# Linear_Regulator_LT3042.net
KiCad netlist of a schematic drawn in EAGLE
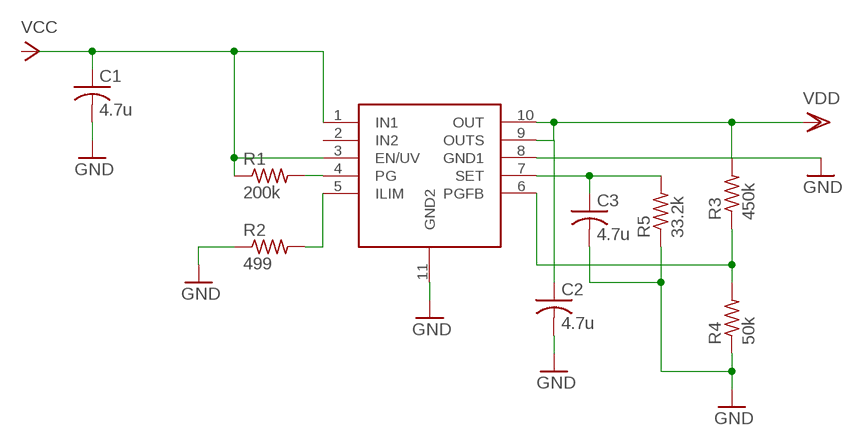
[diagram p0: schematic, sheet 1]

(export (version "E")
  (design (tool "Eeschema 10.0.6"))
  (components
    (comp (ref "C1")
      (value "4.7u")
      (footprint "eagle-import:C0603")
      (libsource (lib "eagle-import") (part "C-USC0603"))
    )
    (comp (ref "C2")
      (value "4.7u")
      (footprint "eagle-import:C0603")
      (libsource (lib "eagle-import") (part "C-USC0603"))
    )
    (comp (ref "C3")
      (value "4.7u")
      (footprint "eagle-import:C0603")
      (libsource (lib "eagle-import") (part "C-USC0603"))
    )
    (comp (ref "R1")
      (value "200k")
      (footprint "eagle-import:R0603")
      (libsource (lib "eagle-import") (part "R-US_R0603"))
    )
    (comp (ref "R2")
      (value "499")
      (footprint "eagle-import:R0603")
      (libsource (lib "eagle-import") (part "R-US_R0603"))
    )
    (comp (ref "R3")
      (value "450k")
      (footprint "eagle-import:R0603")
      (libsource (lib "eagle-import") (part "R-US_R0603"))
    )
    (comp (ref "R4")
      (value "50k")
      (footprint "eagle-import:R0603")
      (libsource (lib "eagle-import") (part "R-US_R0603"))
    )
    (comp (ref "R5")
      (value "33.2k")
      (footprint "eagle-import:R0603")
      (libsource (lib "eagle-import") (part "R-US_R0603"))
    )
    (comp (ref "U$1")
      (value "LT3042")
      (footprint "eagle-import:LT3042")
      (libsource (lib "eagle-import") (part "LT3042"))
    )
  )
  (nets
    (net (code "1") (name "GND") (class "Default")
      (node (ref "C1") (pin "2") (pinfunction "2_2") (pintype "passive"))
      (node (ref "C2") (pin "2") (pinfunction "2_2") (pintype "passive"))
      (node (ref "C3") (pin "2") (pinfunction "2_2") (pintype "passive"))
      (node (ref "R2") (pin "1") (pinfunction "1_1") (pintype "passive"))
      (node (ref "R4") (pin "1") (pinfunction "1_1") (pintype "passive"))
      (node (ref "R5") (pin "1") (pinfunction "1_1") (pintype "passive"))
      (node (ref "U$1") (pin "11") (pinfunction "GND2_11") (pintype "power_in"))
      (node (ref "U$1") (pin "8") (pinfunction "GND1_8") (pintype "power_in"))
    )
    (net (code "2") (name "Net-(U$1-EN{slash}UV)") (class "Default")
      (node (ref "C1") (pin "1") (pinfunction "1_1") (pintype "passive"))
      (node (ref "R1") (pin "1") (pinfunction "1_1") (pintype "passive"))
      (node (ref "U$1") (pin "1") (pinfunction "IN1_1") (pintype "input"))
      (node (ref "U$1") (pin "3") (pinfunction "EN/UV_3") (pintype "input"))
    )
    (net (code "3") (name "Net-(U$1-ILIM)") (class "Default")
      (node (ref "R2") (pin "2") (pinfunction "2_2") (pintype "passive"))
      (node (ref "U$1") (pin "5") (pinfunction "ILIM_5") (pintype "input"))
    )
    (net (code "4") (name "Net-(U$1-PG)") (class "Default")
      (node (ref "R1") (pin "2") (pinfunction "2_2") (pintype "passive"))
      (node (ref "U$1") (pin "4") (pinfunction "PG_4") (pintype "input"))
    )
    (net (code "5") (name "Net-(U$1-PGFB)") (class "Default")
      (node (ref "R3") (pin "1") (pinfunction "1_1") (pintype "passive"))
      (node (ref "R4") (pin "2") (pinfunction "2_2") (pintype "passive"))
      (node (ref "U$1") (pin "6") (pinfunction "PGFB_6") (pintype "bidirectional"))
    )
    (net (code "6") (name "Net-(U$1-SET)") (class "Default")
      (node (ref "C3") (pin "1") (pinfunction "1_1") (pintype "passive"))
      (node (ref "R5") (pin "2") (pinfunction "2_2") (pintype "passive"))
      (node (ref "U$1") (pin "7") (pinfunction "SET_7") (pintype "input"))
    )
    (net (code "8") (name "VDD") (class "Default")
      (node (ref "C2") (pin "1") (pinfunction "1_1") (pintype "passive"))
      (node (ref "R3") (pin "2") (pinfunction "2_2") (pintype "passive"))
      (node (ref "U$1") (pin "10") (pinfunction "OUT_10") (pintype "output"))
      (node (ref "U$1") (pin "9") (pinfunction "OUTS_9") (pintype "input"))
    )
    (net (code "9") (name "unconnected-(U$1-IN2-Pad2)") (class "Default")
      (node (ref "U$1") (pin "2") (pinfunction "IN2_2") (pintype "input"))
    )
  )
)
